# pidshield-mk-2_1.net
KiCad netlist of a schematic drawn in EAGLE
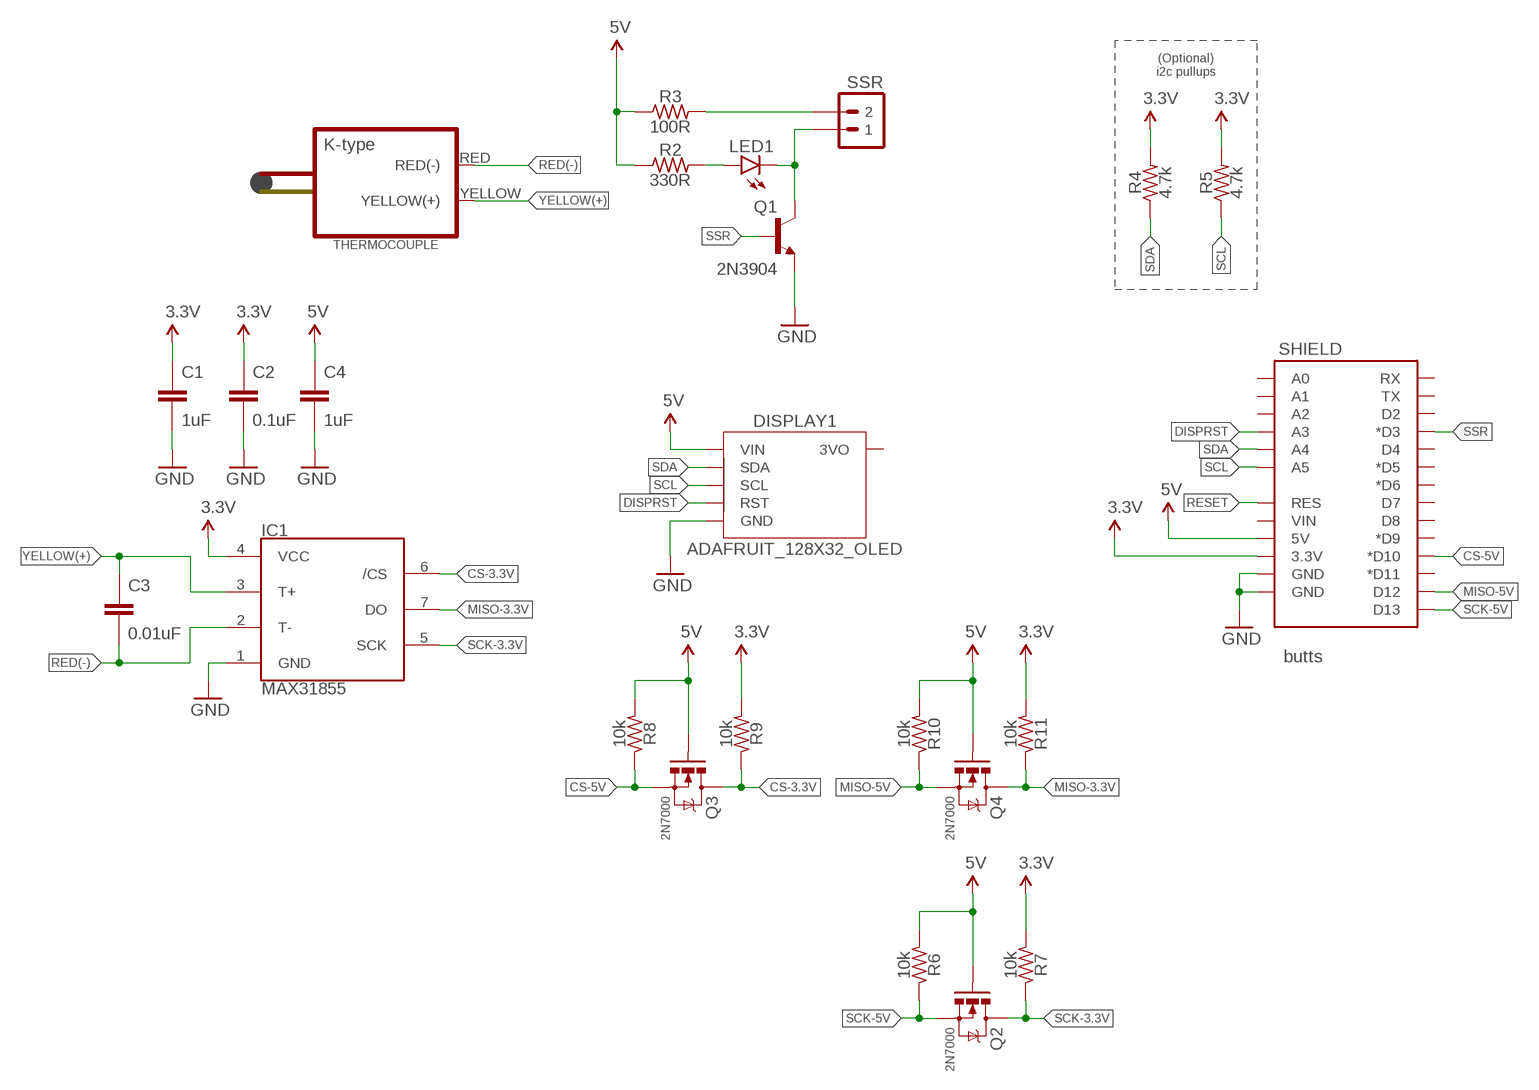
[diagram p0: schematic, sheet 1]

(export (version "E")
  (design (tool "Eeschema 10.0.6"))
  (components
    (comp (ref "C1")
      (value "1uF")
      (footprint "eagle-import:C025-024X044")
      (libsource (lib "eagle-import") (part "CAPACITOR-CERAMIC025-024X044"))
    )
    (comp (ref "C2")
      (value "0.1uF")
      (footprint "eagle-import:C025-024X044")
      (libsource (lib "eagle-import") (part "CAPACITOR-CERAMIC025-024X044"))
    )
    (comp (ref "C3")
      (value "0.01uF")
      (footprint "eagle-import:C0805")
      (libsource (lib "eagle-import") (part "CAPACITOR-CERAMICC0805"))
    )
    (comp (ref "C4")
      (value "1uF")
      (footprint "eagle-import:C025-024X044")
      (libsource (lib "eagle-import") (part "CAPACITOR-CERAMIC025-024X044"))
    )
    (comp (ref "DISPLAY1")
      (value "ADAFRUIT_128X32_OLED")
      (footprint "eagle-import:ADAFRUIT_128X32_OLED_I2C_CLOSER_NS")
      (libsource (lib "eagle-import") (part "ADAFRUIT_128X32_OLED_I2CNOSILK_NOHOLES_NOPROBLEM"))
    )
    (comp (ref "IC1")
      (value "MAX31855")
      (footprint "eagle-import:SOIC127P600X175-8N")
      (libsource (lib "eagle-import") (part "MAX31855SOIC"))
    )
    (comp (ref "LED1")
      (value "LED3MM-LESS")
      (footprint "eagle-import:LED3MM-LESSSILK")
      (libsource (lib "eagle-import") (part "LED3MM-LESS"))
    )
    (comp (ref "Q1")
      (value "2N3904")
      (footprint "eagle-import:TO-92-AMMO")
      (libsource (lib "eagle-import") (part "TRANSISTOR_NPNTO-92-AMMO-EBC"))
    )
    (comp (ref "Q2")
      (value "2N7000")
      (footprint "eagle-import:TO-92-AMMO")
      (libsource (lib "eagle-import") (part "MOSFET-NCHANNEL2N7000-AMMO"))
    )
    (comp (ref "Q3")
      (value "2N7000")
      (footprint "eagle-import:TO-92-AMMO")
      (libsource (lib "eagle-import") (part "MOSFET-NCHANNEL2N7000-AMMO"))
    )
    (comp (ref "Q4")
      (value "2N7000")
      (footprint "eagle-import:TO-92-AMMO")
      (libsource (lib "eagle-import") (part "MOSFET-NCHANNEL2N7000-AMMO"))
    )
    (comp (ref "R2")
      (value "330R")
      (footprint "eagle-import:RESISTOR-AXIAL-PTH-5.08MM")
      (libsource (lib "eagle-import") (part "RESISTORPTH-AXIAL-5.08MM"))
    )
    (comp (ref "R3")
      (value "100R")
      (footprint "eagle-import:RESISTOR-AXIAL-PTH-5.08MM")
      (libsource (lib "eagle-import") (part "RESISTORPTH-AXIAL-5.08MM"))
    )
    (comp (ref "R4")
      (value "4.7k")
      (footprint "eagle-import:RESISTOR-AXIAL-PTH-5.08MM")
      (libsource (lib "eagle-import") (part "RESISTORPTH-AXIAL-5.08MM"))
    )
    (comp (ref "R5")
      (value "4.7k")
      (footprint "eagle-import:RESISTOR-AXIAL-PTH-5.08MM")
      (libsource (lib "eagle-import") (part "RESISTORPTH-AXIAL-5.08MM"))
    )
    (comp (ref "R6")
      (value "10k")
      (footprint "eagle-import:RESISTOR-AXIAL-PTH-5.08MM")
      (libsource (lib "eagle-import") (part "RESISTORPTH-AXIAL-5.08MM"))
    )
    (comp (ref "R7")
      (value "10k")
      (footprint "eagle-import:RESISTOR-AXIAL-PTH-5.08MM")
      (libsource (lib "eagle-import") (part "RESISTORPTH-AXIAL-5.08MM"))
    )
    (comp (ref "R8")
      (value "10k")
      (footprint "eagle-import:RESISTOR-AXIAL-PTH-5.08MM")
      (libsource (lib "eagle-import") (part "RESISTORPTH-AXIAL-5.08MM"))
    )
    (comp (ref "R9")
      (value "10k")
      (footprint "eagle-import:RESISTOR-AXIAL-PTH-5.08MM")
      (libsource (lib "eagle-import") (part "RESISTORPTH-AXIAL-5.08MM"))
    )
    (comp (ref "R10")
      (value "10k")
      (footprint "eagle-import:RESISTOR-AXIAL-PTH-5.08MM")
      (libsource (lib "eagle-import") (part "RESISTORPTH-AXIAL-5.08MM"))
    )
    (comp (ref "R11")
      (value "10k")
      (footprint "eagle-import:RESISTOR-AXIAL-PTH-5.08MM")
      (libsource (lib "eagle-import") (part "RESISTORPTH-AXIAL-5.08MM"))
    )
    (comp (ref "SHIELD")
      (value "butts")
      (footprint "eagle-import:ARDUINO_SHIELD_NOOUTLINE_INSIDE_SMALLER")
      (libsource (lib "eagle-import") (part "ARDUINO_SHIELD_SMALLER"))
    )
    (comp (ref "SSR")
      (value "M02JST-PTH-RA-SMALLPADS")
      (footprint "eagle-import:JST-2-PH-RA-PTH-SMALLPADS")
      (libsource (lib "eagle-import") (part "M02JST-PTH-RA-SMALLPADS"))
    )
    (comp (ref "THERMOCOUPLE")
      (value "THERMOCOUPLE-CONNECTORMINI-PCB")
      (footprint "eagle-import:PCC-SMP")
      (libsource (lib "eagle-import") (part "THERMOCOUPLE-CONNECTORMINI-PCB"))
    )
  )
  (nets
    (net (code "1") (name "3.3V") (class "Default")
      (node (ref "C1") (pin "1") (pinfunction "1_1") (pintype "passive"))
      (node (ref "C2") (pin "1") (pinfunction "1_1") (pintype "passive"))
      (node (ref "IC1") (pin "4") (pinfunction "VCC_4") (pintype "power_in"))
      (node (ref "R11") (pin "P$2") (pinfunction "2_P$2") (pintype "passive"))
      (node (ref "R4") (pin "P$2") (pinfunction "2_P$2") (pintype "passive"))
      (node (ref "R5") (pin "P$2") (pinfunction "2_P$2") (pintype "passive"))
      (node (ref "R7") (pin "P$2") (pinfunction "2_P$2") (pintype "passive"))
      (node (ref "R9") (pin "P$2") (pinfunction "2_P$2") (pintype "passive"))
      (node (ref "SHIELD") (pin "3.3V") (pinfunction "3.3V_3.3V") (pintype "bidirectional"))
    )
    (net (code "2") (name "5V") (class "Default")
      (node (ref "C4") (pin "1") (pinfunction "1_1") (pintype "passive"))
      (node (ref "DISPLAY1") (pin "VIN") (pinfunction "VIN_VIN") (pintype "bidirectional"))
      (node (ref "Q2") (pin "2") (pinfunction "G_2") (pintype "passive"))
      (node (ref "Q3") (pin "2") (pinfunction "G_2") (pintype "passive"))
      (node (ref "Q4") (pin "2") (pinfunction "G_2") (pintype "passive"))
      (node (ref "R10") (pin "P$2") (pinfunction "2_P$2") (pintype "passive"))
      (node (ref "R2") (pin "P$1") (pinfunction "1_P$1") (pintype "passive"))
      (node (ref "R3") (pin "P$1") (pinfunction "1_P$1") (pintype "passive"))
      (node (ref "R6") (pin "P$2") (pinfunction "2_P$2") (pintype "passive"))
      (node (ref "R8") (pin "P$2") (pinfunction "2_P$2") (pintype "passive"))
      (node (ref "SHIELD") (pin "5V") (pinfunction "5V_5V") (pintype "bidirectional"))
    )
    (net (code "3") (name "CS-3.3V") (class "Default")
      (node (ref "IC1") (pin "6") (pinfunction "/CS_6") (pintype "input"))
      (node (ref "Q3") (pin "3") (pinfunction "D_3") (pintype "passive"))
      (node (ref "R9") (pin "P$1") (pinfunction "1_P$1") (pintype "passive"))
    )
    (net (code "4") (name "CS-5V") (class "Default")
      (node (ref "Q3") (pin "1") (pinfunction "S_1") (pintype "passive"))
      (node (ref "R8") (pin "P$1") (pinfunction "1_P$1") (pintype "passive"))
      (node (ref "SHIELD") (pin "D10") (pinfunction "*D10_D10") (pintype "bidirectional"))
    )
    (net (code "5") (name "DISPRST") (class "Default")
      (node (ref "DISPLAY1") (pin "RST") (pinfunction "RST_RST") (pintype "bidirectional"))
      (node (ref "SHIELD") (pin "A3") (pinfunction "A3_A3") (pintype "bidirectional"))
    )
    (net (code "6") (name "GND") (class "Default")
      (node (ref "C1") (pin "2") (pinfunction "2_2") (pintype "passive"))
      (node (ref "C2") (pin "2") (pinfunction "2_2") (pintype "passive"))
      (node (ref "C4") (pin "2") (pinfunction "2_2") (pintype "passive"))
      (node (ref "DISPLAY1") (pin "GND") (pinfunction "GND_GND") (pintype "bidirectional"))
      (node (ref "IC1") (pin "1") (pinfunction "GND_1") (pintype "power_in"))
      (node (ref "Q1") (pin "1") (pinfunction "E_1") (pintype "passive"))
      (node (ref "SHIELD") (pin "GND@0") (pinfunction "GND_GND@0") (pintype "bidirectional"))
      (node (ref "SHIELD") (pin "GND@1") (pinfunction "GND_GND@1") (pintype "bidirectional"))
    )
    (net (code "7") (name "MISO-3.3V") (class "Default")
      (node (ref "IC1") (pin "7") (pinfunction "DO_7") (pintype "output"))
      (node (ref "Q4") (pin "3") (pinfunction "D_3") (pintype "passive"))
      (node (ref "R11") (pin "P$1") (pinfunction "1_P$1") (pintype "passive"))
    )
    (net (code "8") (name "MISO-5V") (class "Default")
      (node (ref "Q4") (pin "1") (pinfunction "S_1") (pintype "passive"))
      (node (ref "R10") (pin "P$1") (pinfunction "1_P$1") (pintype "passive"))
      (node (ref "SHIELD") (pin "D12") (pinfunction "D12_D12") (pintype "bidirectional"))
    )
    (net (code "9") (name "Net-(LED1-C)") (class "Default")
      (node (ref "LED1") (pin "K") (pinfunction "C_K") (pintype "passive"))
      (node (ref "Q1") (pin "3") (pinfunction "C_3") (pintype "passive"))
      (node (ref "SSR") (pin "1") (pinfunction "1_1") (pintype "passive"))
    )
    (net (code "10") (name "Net-(R2-2)") (class "Default")
      (node (ref "LED1") (pin "A") (pinfunction "A_A") (pintype "passive"))
      (node (ref "R2") (pin "P$2") (pinfunction "2_P$2") (pintype "passive"))
    )
    (net (code "11") (name "Net-(R3-2)") (class "Default")
      (node (ref "R3") (pin "P$2") (pinfunction "2_P$2") (pintype "passive"))
      (node (ref "SSR") (pin "2") (pinfunction "2_2") (pintype "passive"))
    )
    (net (code "12") (name "RED(-)") (class "Default")
      (node (ref "C3") (pin "2") (pinfunction "2_2") (pintype "passive"))
      (node (ref "IC1") (pin "2") (pinfunction "T-_2") (pintype "input"))
      (node (ref "THERMOCOUPLE") (pin "RED") (pinfunction "RED(-)_RED") (pintype "bidirectional"))
    )
    (net (code "13") (name "RESET") (class "Default")
      (node (ref "SHIELD") (pin "RES") (pinfunction "RES_RES") (pintype "bidirectional"))
    )
    (net (code "14") (name "SCK-3.3V") (class "Default")
      (node (ref "IC1") (pin "5") (pinfunction "SCK_5") (pintype "input"))
      (node (ref "Q2") (pin "3") (pinfunction "D_3") (pintype "passive"))
      (node (ref "R7") (pin "P$1") (pinfunction "1_P$1") (pintype "passive"))
    )
    (net (code "15") (name "SCK-5V") (class "Default")
      (node (ref "Q2") (pin "1") (pinfunction "S_1") (pintype "passive"))
      (node (ref "R6") (pin "P$1") (pinfunction "1_P$1") (pintype "passive"))
      (node (ref "SHIELD") (pin "D13") (pinfunction "D13_D13") (pintype "bidirectional"))
    )
    (net (code "16") (name "SCL") (class "Default")
      (node (ref "DISPLAY1") (pin "SCL") (pinfunction "SCL_SCL") (pintype "bidirectional"))
      (node (ref "R5") (pin "P$1") (pinfunction "1_P$1") (pintype "passive"))
      (node (ref "SHIELD") (pin "A5") (pinfunction "A5_A5") (pintype "bidirectional"))
    )
    (net (code "17") (name "SDA") (class "Default")
      (node (ref "DISPLAY1") (pin "SDA") (pinfunction "SDA_SDA") (pintype "bidirectional"))
      (node (ref "R4") (pin "P$1") (pinfunction "1_P$1") (pintype "passive"))
      (node (ref "SHIELD") (pin "A4") (pinfunction "A4_A4") (pintype "bidirectional"))
    )
    (net (code "18") (name "SSR") (class "Default")
      (node (ref "Q1") (pin "2") (pinfunction "B_2") (pintype "passive"))
      (node (ref "SHIELD") (pin "D3") (pinfunction "*D3_D3") (pintype "bidirectional"))
    )
    (net (code "19") (name "YELLOW(+)") (class "Default")
      (node (ref "C3") (pin "1") (pinfunction "1_1") (pintype "passive"))
      (node (ref "IC1") (pin "3") (pinfunction "T+_3") (pintype "input"))
      (node (ref "THERMOCOUPLE") (pin "YELLOW") (pinfunction "YELLOW(+)_YELLOW") (pintype "bidirectional"))
    )
    (net (code "20") (name "unconnected-(DISPLAY1-Pad3VO)") (class "Default")
      (node (ref "DISPLAY1") (pin "3VO") (pinfunction "3VO_3VO") (pintype "bidirectional"))
    )
    (net (code "21") (name "unconnected-(SHIELD-*D5-PadD5)") (class "Default")
      (node (ref "SHIELD") (pin "D5") (pinfunction "*D5_D5") (pintype "bidirectional"))
    )
    (net (code "22") (name "unconnected-(SHIELD-*D6-PadD6)") (class "Default")
      (node (ref "SHIELD") (pin "D6") (pinfunction "*D6_D6") (pintype "bidirectional"))
    )
    (net (code "23") (name "unconnected-(SHIELD-*D9-PadD9)") (class "Default")
      (node (ref "SHIELD") (pin "D9") (pinfunction "*D9_D9") (pintype "bidirectional"))
    )
    (net (code "24") (name "unconnected-(SHIELD-*D11-PadD11)") (class "Default")
      (node (ref "SHIELD") (pin "D11") (pinfunction "*D11_D11") (pintype "bidirectional"))
    )
    (net (code "25") (name "unconnected-(SHIELD-PadA0)") (class "Default")
      (node (ref "SHIELD") (pin "A0") (pinfunction "A0_A0") (pintype "bidirectional"))
    )
    (net (code "26") (name "unconnected-(SHIELD-PadA1)") (class "Default")
      (node (ref "SHIELD") (pin "A1") (pinfunction "A1_A1") (pintype "bidirectional"))
    )
    (net (code "27") (name "unconnected-(SHIELD-PadA2)") (class "Default")
      (node (ref "SHIELD") (pin "A2") (pinfunction "A2_A2") (pintype "bidirectional"))
    )
    (net (code "28") (name "unconnected-(SHIELD-PadD2)") (class "Default")
      (node (ref "SHIELD") (pin "D2") (pinfunction "D2_D2") (pintype "bidirectional"))
    )
    (net (code "29") (name "unconnected-(SHIELD-PadD4)") (class "Default")
      (node (ref "SHIELD") (pin "D4") (pinfunction "D4_D4") (pintype "bidirectional"))
    )
    (net (code "30") (name "unconnected-(SHIELD-PadD7)") (class "Default")
      (node (ref "SHIELD") (pin "D7") (pinfunction "D7_D7") (pintype "bidirectional"))
    )
    (net (code "31") (name "unconnected-(SHIELD-PadD8)") (class "Default")
      (node (ref "SHIELD") (pin "D8") (pinfunction "D8_D8") (pintype "bidirectional"))
    )
    (net (code "32") (name "unconnected-(SHIELD-PadRX)") (class "Default")
      (node (ref "SHIELD") (pin "RX") (pinfunction "RX_RX") (pintype "bidirectional"))
    )
    (net (code "33") (name "unconnected-(SHIELD-PadTX)") (class "Default")
      (node (ref "SHIELD") (pin "TX") (pinfunction "TX_TX") (pintype "bidirectional"))
    )
    (net (code "34") (name "unconnected-(SHIELD-PadVIN)") (class "Default")
      (node (ref "SHIELD") (pin "VIN") (pinfunction "VIN_VIN") (pintype "bidirectional"))
    )
  )
)
